# Breadboard_potentiometer_adapter.net
KiCad netlist of a schematic drawn in EasyEDA
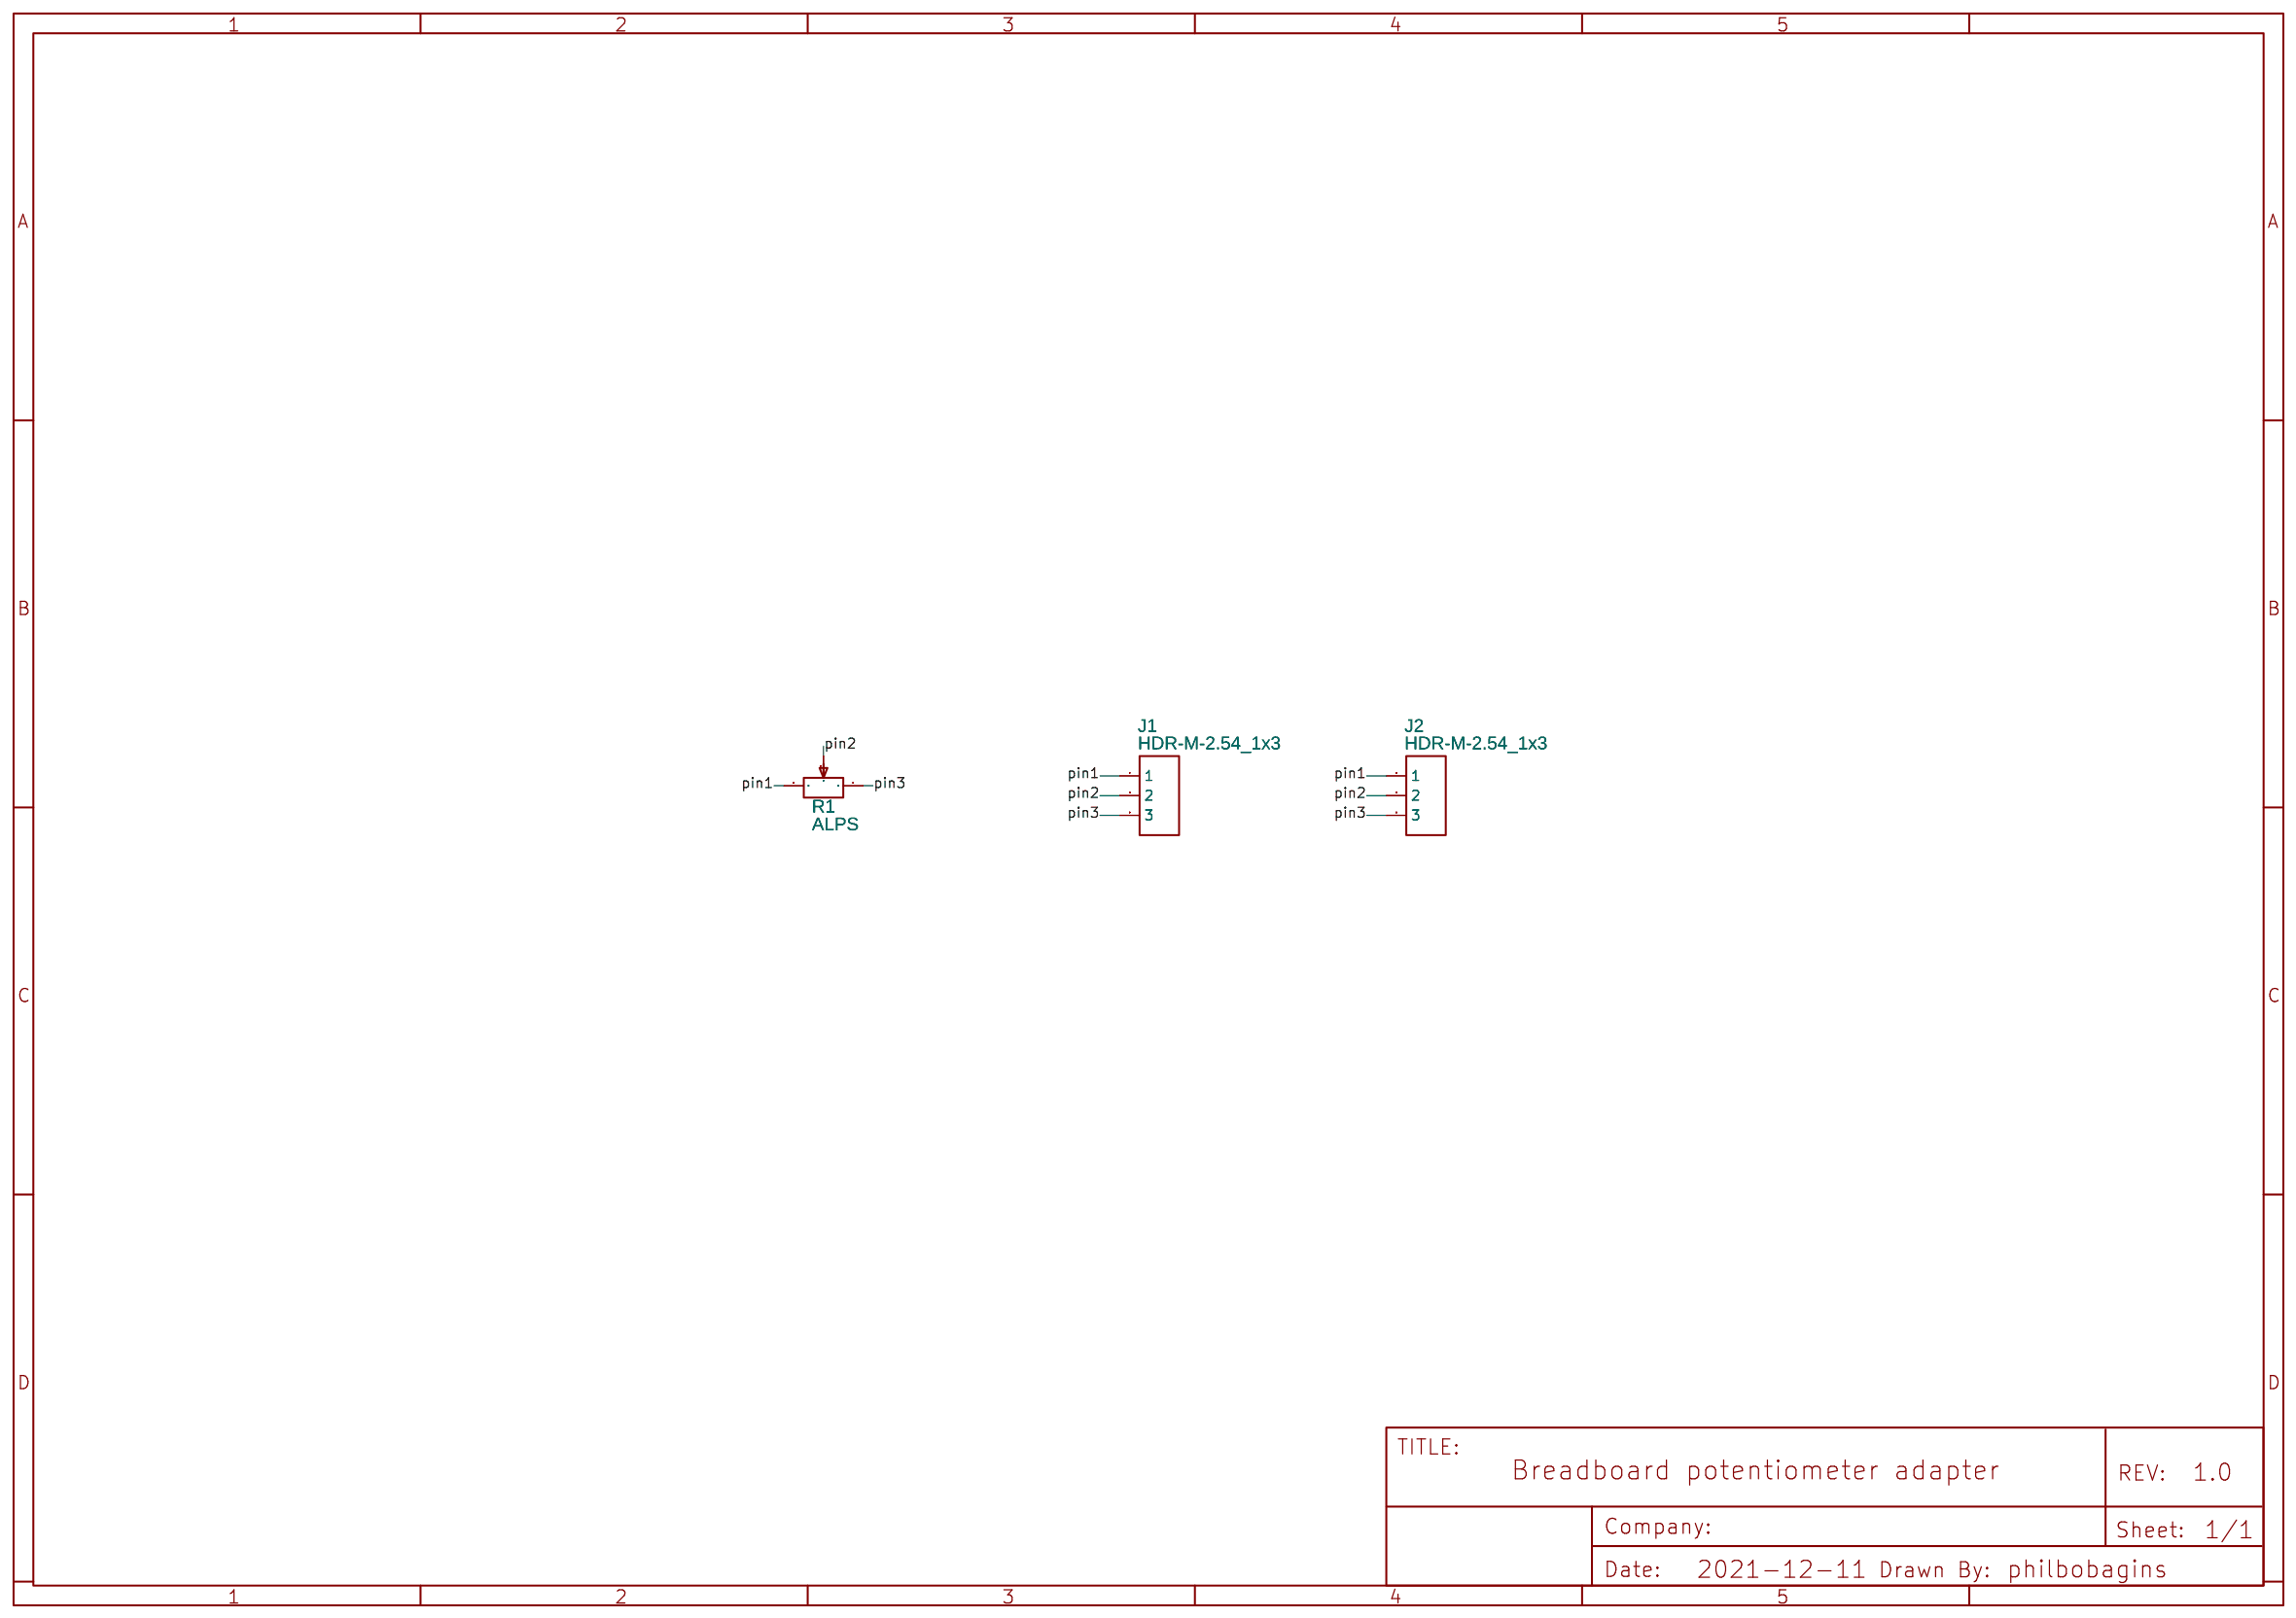
[diagram p0: schematic sheet]

(export (version "E")
  (design (tool "Eeschema 10.0.6"))
  (components
    (comp (ref "J1")
      (value "HDR-M-2.54_1x3")
      (fields (field (name "BOM_Supplier Part") "C180248"))
      (libsource (lib "") (part "HDR-M-2.54_1x3"))
    )
    (comp (ref "J2")
      (value "HDR-M-2.54_1x3")
      (fields (field (name "BOM_Supplier Part") "C180248"))
      (libsource (lib "") (part "HDR-M-2.54_1x3"))
    )
    (comp (ref "R1")
      (value "ALPS")
      (fields
        (field (name "BOM_Manufacturer Part") "RK1631110TT3")
        (field (name "BOM_Supplier Part") "C370977")
      )
      (libsource (lib "") (part "RK1631110TT3"))
    )
  )
  (nets
    (net (code "1") (name "/pin1") (class "Default")
      (node (ref "J1") (pin "1") (pinfunction "1_1") (pintype "input"))
      (node (ref "J2") (pin "1") (pinfunction "1_1") (pintype "input"))
      (node (ref "R1") (pin "3") (pinfunction "3_3") (pintype "input"))
    )
    (net (code "2") (name "/pin2") (class "Default")
      (node (ref "J1") (pin "2") (pinfunction "2_2") (pintype "input"))
      (node (ref "J2") (pin "2") (pinfunction "2_2") (pintype "input"))
      (node (ref "R1") (pin "2") (pinfunction "2_2") (pintype "input"))
    )
    (net (code "3") (name "/pin3") (class "Default")
      (node (ref "J1") (pin "3") (pinfunction "3_3") (pintype "input"))
      (node (ref "J2") (pin "3") (pinfunction "3_3") (pintype "input"))
      (node (ref "R1") (pin "1") (pinfunction "1_1") (pintype "input"))
    )
  )
)
